# snarc.net
KiCad netlist of a schematic drawn in EAGLE
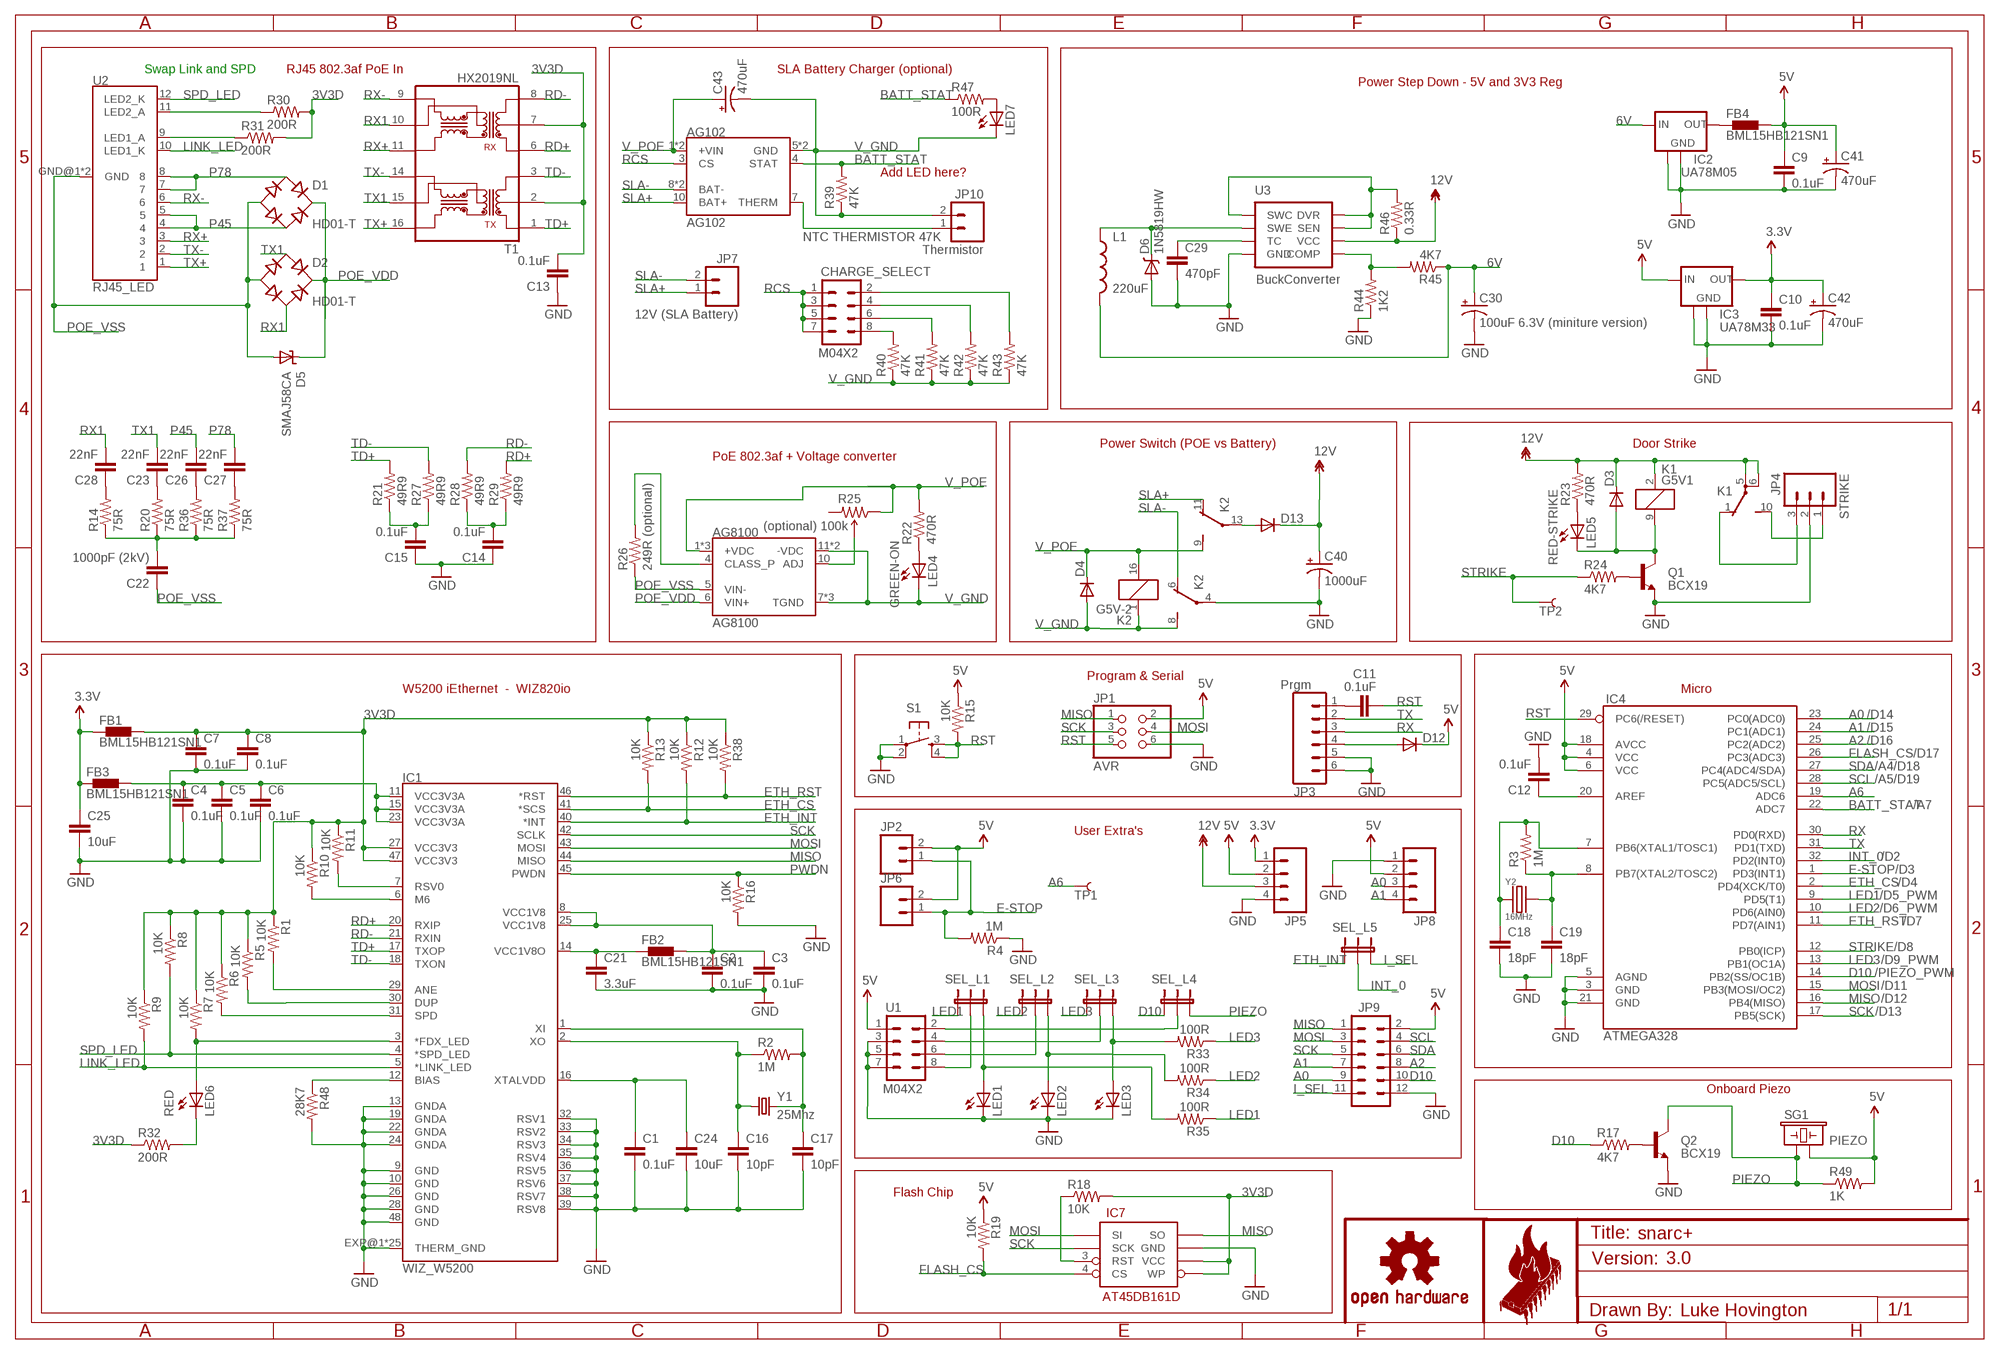
[diagram p0: schematic, sheet 1]

(export (version "E")
  (design (tool "Eeschema 10.0.6"))
  (components
    (comp (ref "AG102")
      (value "AG102")
      (footprint "eagle-import:AG102")
      (libsource (lib "eagle-import") (part "AG102"))
    )
    (comp (ref "AG8100")
      (value "AG8100")
      (footprint "eagle-import:AG8100")
      (libsource (lib "eagle-import") (part "AG8100"))
    )
    (comp (ref "C1")
      (value "0.1uF")
      (footprint "eagle-import:0402-CAP")
      (libsource (lib "eagle-import") (part "CAP0402-CAP"))
    )
    (comp (ref "C2")
      (value "0.1uF")
      (footprint "eagle-import:0402-CAP")
      (libsource (lib "eagle-import") (part "CAP0402-CAP"))
    )
    (comp (ref "C3")
      (value "0.1uF")
      (footprint "eagle-import:0402-CAP")
      (libsource (lib "eagle-import") (part "CAP0402-CAP"))
    )
    (comp (ref "C4")
      (value "0.1uF")
      (footprint "eagle-import:0402-CAP")
      (libsource (lib "eagle-import") (part "CAP0402-CAP"))
    )
    (comp (ref "C5")
      (value "0.1uF")
      (footprint "eagle-import:0402-CAP")
      (libsource (lib "eagle-import") (part "CAP0402-CAP"))
    )
    (comp (ref "C6")
      (value "0.1uF")
      (footprint "eagle-import:0402-CAP")
      (libsource (lib "eagle-import") (part "CAP0402-CAP"))
    )
    (comp (ref "C7")
      (value "0.1uF")
      (footprint "eagle-import:0402-CAP")
      (libsource (lib "eagle-import") (part "CAP0402-CAP"))
    )
    (comp (ref "C8")
      (value "0.1uF")
      (footprint "eagle-import:0402-CAP")
      (libsource (lib "eagle-import") (part "CAP0402-CAP"))
    )
    (comp (ref "C9")
      (value "0.1uF")
      (footprint "eagle-import:0402-CAP")
      (libsource (lib "eagle-import") (part "CAP0402-CAP"))
    )
    (comp (ref "C10")
      (value "0.1uF")
      (footprint "eagle-import:0402-CAP")
      (libsource (lib "eagle-import") (part "CAP0402-CAP"))
    )
    (comp (ref "C11")
      (value "0.1uF")
      (footprint "eagle-import:0402-CAP")
      (libsource (lib "eagle-import") (part "CAP0402-CAP"))
    )
    (comp (ref "C12")
      (value "0.1uF")
      (footprint "eagle-import:0402-CAP")
      (libsource (lib "eagle-import") (part "CAP0402-CAP"))
    )
    (comp (ref "C13")
      (value "0.1uF")
      (footprint "eagle-import:0402-CAP")
      (libsource (lib "eagle-import") (part "CAP0402-CAP"))
    )
    (comp (ref "C14")
      (value "0.1uF")
      (footprint "eagle-import:0402-CAP")
      (libsource (lib "eagle-import") (part "CAP0402-CAP"))
    )
    (comp (ref "C15")
      (value "0.1uF")
      (footprint "eagle-import:0402-CAP")
      (libsource (lib "eagle-import") (part "CAP0402-CAP"))
    )
    (comp (ref "C16")
      (value "10pF")
      (footprint "eagle-import:0402-CAP")
      (libsource (lib "eagle-import") (part "CAP0402-CAP"))
    )
    (comp (ref "C17")
      (value "10pF")
      (footprint "eagle-import:0402-CAP")
      (libsource (lib "eagle-import") (part "CAP0402-CAP"))
    )
    (comp (ref "C18")
      (value "18pF")
      (footprint "eagle-import:0402-CAP")
      (libsource (lib "eagle-import") (part "CAP0402-CAP"))
    )
    (comp (ref "C19")
      (value "18pF")
      (footprint "eagle-import:0402-CAP")
      (libsource (lib "eagle-import") (part "CAP0402-CAP"))
    )
    (comp (ref "C21")
      (value "3.3uF")
      (footprint "eagle-import:0402-CAP")
      (libsource (lib "eagle-import") (part "CAP0402-CAP"))
    )
    (comp (ref "C22")
      (value "1000pF (2kV)")
      (footprint "eagle-import:0402-CAP")
      (libsource (lib "eagle-import") (part "CAP0402-CAP"))
    )
    (comp (ref "C23")
      (value "22nF")
      (footprint "eagle-import:0402-CAP")
      (libsource (lib "eagle-import") (part "CAP0402-CAP"))
    )
    (comp (ref "C24")
      (value "10uF")
      (footprint "eagle-import:0603-CAP")
      (libsource (lib "eagle-import") (part "CAP0603-CAP"))
    )
    (comp (ref "C25")
      (value "10uF")
      (footprint "eagle-import:0603-CAP")
      (libsource (lib "eagle-import") (part "CAP0603-CAP"))
    )
    (comp (ref "C26")
      (value "22nF")
      (footprint "eagle-import:0402-CAP")
      (libsource (lib "eagle-import") (part "CAP0402-CAP"))
    )
    (comp (ref "C27")
      (value "22nF")
      (footprint "eagle-import:0402-CAP")
      (libsource (lib "eagle-import") (part "CAP0402-CAP"))
    )
    (comp (ref "C28")
      (value "22nF")
      (footprint "eagle-import:0402-CAP")
      (libsource (lib "eagle-import") (part "CAP0402-CAP"))
    )
    (comp (ref "C29")
      (value "470pF")
      (footprint "eagle-import:0402-CAP")
      (libsource (lib "eagle-import") (part "CAP0402-CAP"))
    )
    (comp (ref "C30")
      (value "100uF 6.3V (miniture version)")
      (footprint "eagle-import:PANASONIC_C")
      (libsource (lib "eagle-import") (part "CAP_POLC"))
    )
    (comp (ref "C40")
      (value "1000uF")
      (footprint "eagle-import:PANASONIC_H13")
      (libsource (lib "eagle-import") (part "CAP_POLH13"))
    )
    (comp (ref "C41")
      (value "470uF")
      (footprint "eagle-import:PANASONIC_E")
      (libsource (lib "eagle-import") (part "CAP_POLE"))
    )
    (comp (ref "C42")
      (value "470uF")
      (footprint "eagle-import:PANASONIC_E")
      (libsource (lib "eagle-import") (part "CAP_POLE"))
    )
    (comp (ref "C43")
      (value "470uF")
      (footprint "eagle-import:PANASONIC_E")
      (libsource (lib "eagle-import") (part "CAP_POLE"))
    )
    (comp (ref "CHARGE_SELECT")
      (value "M04X2")
      (footprint "eagle-import:2X4")
      (libsource (lib "eagle-import") (part "M04X2"))
    )
    (comp (ref "D1")
      (value "HD01-T")
      (footprint "eagle-import:MBS")
      (libsource (lib "eagle-import") (part "BS1"))
    )
    (comp (ref "D2")
      (value "HD01-T")
      (footprint "eagle-import:MBS")
      (libsource (lib "eagle-import") (part "BS1"))
    )
    (comp (ref "D3")
      (value "DIODESOD")
      (footprint "eagle-import:SOD-323")
      (libsource (lib "eagle-import") (part "DIODESOD"))
    )
    (comp (ref "D4")
      (value "DIODESOD")
      (footprint "eagle-import:SOD-323")
      (libsource (lib "eagle-import") (part "DIODESOD"))
    )
    (comp (ref "D5")
      (value "SMAJ58CA")
      (footprint "eagle-import:SMBJ")
      (libsource (lib "eagle-import") (part "SUPPRESSOR-SMBJ"))
    )
    (comp (ref "D6")
      (value "1N5819HW")
      (footprint "eagle-import:SOD-123")
      (libsource (lib "eagle-import") (part "DIODE-SCHOTTKYSOD-123"))
    )
    (comp (ref "D12")
      (value "DIODESOD")
      (footprint "eagle-import:SOD-323")
      (libsource (lib "eagle-import") (part "DIODESOD"))
    )
    (comp (ref "D13")
      (value "DIODESOD")
      (footprint "eagle-import:SOD-323")
      (libsource (lib "eagle-import") (part "DIODESOD"))
    )
    (comp (ref "FB1")
      (value "BML15HB121SN1")
      (footprint "eagle-import:0402")
      (libsource (lib "eagle-import") (part "BML15HB121SN1"))
    )
    (comp (ref "FB2")
      (value "BML15HB121SN1")
      (footprint "eagle-import:0402")
      (libsource (lib "eagle-import") (part "BML15HB121SN1"))
    )
    (comp (ref "FB3")
      (value "BML15HB121SN1")
      (footprint "eagle-import:0402")
      (libsource (lib "eagle-import") (part "BML15HB121SN1"))
    )
    (comp (ref "FB4")
      (value "BML15HB121SN1")
      (footprint "eagle-import:0402")
      (libsource (lib "eagle-import") (part "BML15HB121SN1"))
    )
    (comp (ref "IC1")
      (value "WIZ_W5200")
      (footprint "eagle-import:QFN48")
      (libsource (lib "eagle-import") (part "WIZ_W5200"))
    )
    (comp (ref "IC2")
      (value "UA78M05")
      (footprint "eagle-import:SOT223")
      (libsource (lib "eagle-import") (part "V_REG_SOTXXX"))
    )
    (comp (ref "IC3")
      (value "UA78M33")
      (footprint "eagle-import:SOT223")
      (libsource (lib "eagle-import") (part "V_REG_SOTXXX"))
    )
    (comp (ref "IC4")
      (value "ATMEGA328")
      (footprint "eagle-import:TQFP32-08")
      (libsource (lib "eagle-import") (part "ATMEGA168"))
    )
    (comp (ref "IC7")
      (value "AT45DB161D")
      (footprint "eagle-import:SO08-EIAJ")
      (libsource (lib "eagle-import") (part "AT45DB161D"))
    )
    (comp (ref "JP1")
      (value "AVR")
      (footprint "eagle-import:2X03")
      (libsource (lib "eagle-import") (part "PINHD-2X3"))
    )
    (comp (ref "JP2")
      (value "M023.5MM")
      (footprint "eagle-import:SCREWTERMINAL-3.5MM-2")
      (libsource (lib "eagle-import") (part "M023.5MM"))
    )
    (comp (ref "JP3")
      (value "Prgm")
      (footprint "eagle-import:1X06_SMD_STRAIGHT")
      (libsource (lib "eagle-import") (part "M06SMD-STRAIGHT"))
    )
    (comp (ref "JP4")
      (value "STRIKE")
      (footprint "eagle-import:SCREWTERMINAL-3.5MM-3")
      (libsource (lib "eagle-import") (part "M03SCREW"))
    )
    (comp (ref "JP5")
      (value "M04SMD")
      (footprint "eagle-import:1X04-SMD")
      (libsource (lib "eagle-import") (part "M04SMD"))
    )
    (comp (ref "JP6")
      (value "M021X02_NO_SILK")
      (footprint "eagle-import:1X02_NO_SILK")
      (libsource (lib "eagle-import") (part "M021X02_NO_SILK"))
    )
    (comp (ref "JP7")
      (value "12V (SLA Battery)")
      (footprint "eagle-import:SCREWTERMINAL-3.5MM-2")
      (libsource (lib "eagle-import") (part "M023.5MM"))
    )
    (comp (ref "JP8")
      (value "M04POLAR")
      (footprint "eagle-import:MOLEX-1X4")
      (libsource (lib "eagle-import") (part "M04POLAR"))
    )
    (comp (ref "JP9")
      (value "M05x2_SMD")
      (footprint "eagle-import:2X6-SHROUDED_SMD")
      (libsource (lib "eagle-import") (part "M06X2"))
    )
    (comp (ref "JP10")
      (value "Thermistor")
      (footprint "eagle-import:SCREWTERMINAL-3.5MM-2")
      (libsource (lib "eagle-import") (part "M023.5MM"))
    )
    (comp (ref "K1")
      (value "G5V1")
      (footprint "eagle-import:G5V1")
      (fields
        (field (name "MPN") "G5V-1-DC24")
        (field (name "MPN_1") "G5V-1-DC24")
        (field (name "OC_FARNELL") "9949593")
        (field (name "OC_NEWARK") "36M6377")
      )
      (libsource (lib "eagle-import") (part "G5V1"))
    )
    (comp (ref "K2")
      (value "G5V-2")
      (footprint "eagle-import:G5V-2")
      (fields (field (name "MPN") "G5V-2 5DC"))
      (libsource (lib "eagle-import") (part "G5V-2"))
    )
    (comp (ref "L1")
      (value "220uF")
      (footprint "eagle-import:SRN")
      (libsource (lib "eagle-import") (part "INDUCTOR"))
    )
    (comp (ref "LED1")
      (value "LED0603")
      (footprint "eagle-import:LED-0603")
      (libsource (lib "eagle-import") (part "LED0603"))
    )
    (comp (ref "LED2")
      (value "LED0603")
      (footprint "eagle-import:LED-0603")
      (libsource (lib "eagle-import") (part "LED0603"))
    )
    (comp (ref "LED3")
      (value "LED0603")
      (footprint "eagle-import:LED-0603")
      (libsource (lib "eagle-import") (part "LED0603"))
    )
    (comp (ref "LED4")
      (value "GREEN-ON")
      (footprint "eagle-import:LED-0603")
      (libsource (lib "eagle-import") (part "LED0603"))
    )
    (comp (ref "LED5")
      (value "RED-STRIKE")
      (footprint "eagle-import:LED-0603")
      (libsource (lib "eagle-import") (part "LED0603"))
    )
    (comp (ref "LED6")
      (value "RED")
      (footprint "eagle-import:LED-0603")
      (libsource (lib "eagle-import") (part "LED0603"))
    )
    (comp (ref "LED7")
      (value "LED0603")
      (footprint "eagle-import:LED-0603")
      (libsource (lib "eagle-import") (part "LED0603"))
    )
    (comp (ref "Q1")
      (value "BCX19")
      (footprint "eagle-import:SOT23-3")
      (libsource (lib "eagle-import") (part "TRANSISTOR_NPNSOT23-3"))
    )
    (comp (ref "Q2")
      (value "BCX19")
      (footprint "eagle-import:SOT23-3")
      (libsource (lib "eagle-import") (part "TRANSISTOR_NPNSOT23-3"))
    )
    (comp (ref "R1")
      (value "10K")
      (footprint "eagle-import:0402-RES")
      (libsource (lib "eagle-import") (part "RESISTOR0402-RES"))
    )
    (comp (ref "R2")
      (value "1M")
      (footprint "eagle-import:0402-RES")
      (libsource (lib "eagle-import") (part "RESISTOR0402-RES"))
    )
    (comp (ref "R3")
      (value "1M")
      (footprint "eagle-import:0402-RES")
      (libsource (lib "eagle-import") (part "RESISTOR0402-RES"))
    )
    (comp (ref "R4")
      (value "1M")
      (footprint "eagle-import:0603-RES")
      (libsource (lib "eagle-import") (part "RESISTOR0603-RES"))
    )
    (comp (ref "R5")
      (value "10K")
      (footprint "eagle-import:0402-RES")
      (libsource (lib "eagle-import") (part "RESISTOR0402-RES"))
    )
    (comp (ref "R6")
      (value "10K")
      (footprint "eagle-import:0402-RES")
      (libsource (lib "eagle-import") (part "RESISTOR0402-RES"))
    )
    (comp (ref "R7")
      (value "10K")
      (footprint "eagle-import:0402-RES")
      (libsource (lib "eagle-import") (part "RESISTOR0402-RES"))
    )
    (comp (ref "R8")
      (value "10K")
      (footprint "eagle-import:0402-RES")
      (libsource (lib "eagle-import") (part "RESISTOR0402-RES"))
    )
    (comp (ref "R9")
      (value "10K")
      (footprint "eagle-import:0402-RES")
      (libsource (lib "eagle-import") (part "RESISTOR0402-RES"))
    )
    (comp (ref "R10")
      (value "10K")
      (footprint "eagle-import:0402-RES")
      (libsource (lib "eagle-import") (part "RESISTOR0402-RES"))
    )
    (comp (ref "R11")
      (value "10K")
      (footprint "eagle-import:0402-RES")
      (libsource (lib "eagle-import") (part "RESISTOR0402-RES"))
    )
    (comp (ref "R12")
      (value "10K")
      (footprint "eagle-import:0402-RES")
      (libsource (lib "eagle-import") (part "RESISTOR0402-RES"))
    )
    (comp (ref "R13")
      (value "10K")
      (footprint "eagle-import:0402-RES")
      (libsource (lib "eagle-import") (part "RESISTOR0402-RES"))
    )
    (comp (ref "R14")
      (value "75R")
      (footprint "eagle-import:0402-RES")
      (libsource (lib "eagle-import") (part "RESISTOR0402-RES"))
    )
    (comp (ref "R15")
      (value "10K")
      (footprint "eagle-import:0402-RES")
      (libsource (lib "eagle-import") (part "RESISTOR0402-RES"))
    )
    (comp (ref "R16")
      (value "10K")
      (footprint "eagle-import:0402-RES")
      (libsource (lib "eagle-import") (part "RESISTOR0402-RES"))
    )
    (comp (ref "R17")
      (value "4K7")
      (footprint "eagle-import:0402-RES")
      (libsource (lib "eagle-import") (part "RESISTOR0402-RES"))
    )
    (comp (ref "R18")
      (value "10K")
      (footprint "eagle-import:0402-RES")
      (libsource (lib "eagle-import") (part "RESISTOR0402-RES"))
    )
    (comp (ref "R19")
      (value "10K")
      (footprint "eagle-import:0402-RES")
      (libsource (lib "eagle-import") (part "RESISTOR0402-RES"))
    )
    (comp (ref "R20")
      (value "75R")
      (footprint "eagle-import:0402-RES")
      (libsource (lib "eagle-import") (part "RESISTOR0402-RES"))
    )
    (comp (ref "R21")
      (value "49R9")
      (footprint "eagle-import:0402-RES")
      (libsource (lib "eagle-import") (part "RESISTOR0402-RES"))
    )
    (comp (ref "R22")
      (value "470R")
      (footprint "eagle-import:0402-RES")
      (libsource (lib "eagle-import") (part "RESISTOR0402-RES"))
    )
    (comp (ref "R23")
      (value "470R")
      (footprint "eagle-import:0402-RES")
      (libsource (lib "eagle-import") (part "RESISTOR0402-RES"))
    )
    (comp (ref "R24")
      (value "4K7")
      (footprint "eagle-import:0402-RES")
      (libsource (lib "eagle-import") (part "RESISTOR0402-RES"))
    )
    (comp (ref "R25")
      (value "(optional) 100k")
      (footprint "eagle-import:TRIMPOT-3MM")
      (libsource (lib "eagle-import") (part "TRIMPOTSMD"))
    )
    (comp (ref "R26")
      (value "249R (optional)")
      (footprint "eagle-import:1206")
      (libsource (lib "eagle-import") (part "RESISTOR1206"))
    )
    (comp (ref "R27")
      (value "49R9")
      (footprint "eagle-import:0402-RES")
      (libsource (lib "eagle-import") (part "RESISTOR0402-RES"))
    )
    (comp (ref "R28")
      (value "49R9")
      (footprint "eagle-import:0402-RES")
      (libsource (lib "eagle-import") (part "RESISTOR0402-RES"))
    )
    (comp (ref "R29")
      (value "49R9")
      (footprint "eagle-import:0402-RES")
      (libsource (lib "eagle-import") (part "RESISTOR0402-RES"))
    )
    (comp (ref "R30")
      (value "200R")
      (footprint "eagle-import:0402-RES")
      (libsource (lib "eagle-import") (part "RESISTOR0402-RES"))
    )
    (comp (ref "R31")
      (value "200R")
      (footprint "eagle-import:0402-RES")
      (libsource (lib "eagle-import") (part "RESISTOR0402-RES"))
    )
    (comp (ref "R32")
      (value "200R")
      (footprint "eagle-import:0402-RES")
      (libsource (lib "eagle-import") (part "RESISTOR0402-RES"))
    )
    (comp (ref "R33")
      (value "100R")
      (footprint "eagle-import:0402-RES")
      (libsource (lib "eagle-import") (part "RESISTOR0402-RES"))
    )
    (comp (ref "R34")
      (value "100R")
      (footprint "eagle-import:0402-RES")
      (libsource (lib "eagle-import") (part "RESISTOR0402-RES"))
    )
    (comp (ref "R35")
      (value "100R")
      (footprint "eagle-import:0402-RES")
      (libsource (lib "eagle-import") (part "RESISTOR0402-RES"))
    )
    (comp (ref "R36")
      (value "75R")
      (footprint "eagle-import:0402-RES")
      (libsource (lib "eagle-import") (part "RESISTOR0402-RES"))
    )
    (comp (ref "R37")
      (value "75R")
      (footprint "eagle-import:0402-RES")
      (libsource (lib "eagle-import") (part "RESISTOR0402-RES"))
    )
    (comp (ref "R38")
      (value "10K")
      (footprint "eagle-import:0402-RES")
      (libsource (lib "eagle-import") (part "RESISTOR0402-RES"))
    )
    (comp (ref "R39")
      (value "47K")
      (footprint "eagle-import:0402-RES")
      (libsource (lib "eagle-import") (part "RESISTOR0402-RES"))
    )
    (comp (ref "R40")
      (value "47K")
      (footprint "eagle-import:0402-RES")
      (libsource (lib "eagle-import") (part "RESISTOR0402-RES"))
    )
    (comp (ref "R41")
      (value "47K")
      (footprint "eagle-import:0402-RES")
      (libsource (lib "eagle-import") (part "RESISTOR0402-RES"))
    )
    (comp (ref "R42")
      (value "47K")
      (footprint "eagle-import:0402-RES")
      (libsource (lib "eagle-import") (part "RESISTOR0402-RES"))
    )
    (comp (ref "R43")
      (value "47K")
      (footprint "eagle-import:0402-RES")
      (libsource (lib "eagle-import") (part "RESISTOR0402-RES"))
    )
    (comp (ref "R44")
      (value "1K2")
      (footprint "eagle-import:0402-RES")
      (libsource (lib "eagle-import") (part "RESISTOR0402-RES"))
    )
    (comp (ref "R45")
      (value "4K7")
      (footprint "eagle-import:0402-RES")
      (libsource (lib "eagle-import") (part "RESISTOR0402-RES"))
    )
    (comp (ref "R46")
      (value "0.33R")
      (footprint "eagle-import:0402-RES")
      (libsource (lib "eagle-import") (part "RESISTOR0402-RES"))
    )
    (comp (ref "R47")
      (value "100R")
      (footprint "eagle-import:0402-RES")
      (libsource (lib "eagle-import") (part "RESISTOR0402-RES"))
    )
    (comp (ref "R48")
      (value "28K7")
      (footprint "eagle-import:0402-RES")
      (libsource (lib "eagle-import") (part "RESISTOR0402-RES"))
    )
    (comp (ref "R49")
      (value "1K")
      (footprint "eagle-import:0402-RES")
      (libsource (lib "eagle-import") (part "RESISTOR0402-RES"))
    )
    (comp (ref "S1")
      (value "TAC_SWITCHSMD")
      (footprint "eagle-import:TACTILE_SWITCH_SMD")
      (libsource (lib "eagle-import") (part "TAC_SWITCHSMD"))
    )
    (comp (ref "SEL_L1")
      (value "JUMPER-32-3")
      (footprint "eagle-import:SJ_3_PASTE2&3")
      (libsource (lib "eagle-import") (part "JUMPER-32-3"))
    )
    (comp (ref "SEL_L2")
      (value "JUMPER-32-3")
      (footprint "eagle-import:SJ_3_PASTE2&3")
      (libsource (lib "eagle-import") (part "JUMPER-32-3"))
    )
    (comp (ref "SEL_L3")
      (value "JUMPER-32-3")
      (footprint "eagle-import:SJ_3_PASTE2&3")
      (libsource (lib "eagle-import") (part "JUMPER-32-3"))
    )
    (comp (ref "SEL_L4")
      (value "JUMPER-32-3")
      (footprint "eagle-import:SJ_3_PASTE2&3")
      (libsource (lib "eagle-import") (part "JUMPER-32-3"))
    )
    (comp (ref "SEL_L5")
      (value "JUMPER-32-3")
      (footprint "eagle-import:SJ_3_PASTE2&3")
      (libsource (lib "eagle-import") (part "JUMPER-32-3"))
    )
    (comp (ref "SG1")
      (value "PIEZO")
      (footprint "eagle-import:PB158-BUZZER")
      (libsource (lib "eagle-import") (part "BUZZER"))
    )
    (comp (ref "T1")
      (value "HX2019NL")
      (footprint "eagle-import:HXXXX")
      (libsource (lib "eagle-import") (part "HX1188"))
    )
    (comp (ref "TP1")
      (value "TEST-POINT3X5")
      (footprint "eagle-import:PAD.03X.05")
      (libsource (lib "eagle-import") (part "TEST-POINT3X5"))
    )
    (comp (ref "TP2")
      (value "TEST-POINT3X5")
      (footprint "eagle-import:PAD.03X.05")
      (libsource (lib "eagle-import") (part "TEST-POINT3X5"))
    )
    (comp (ref "U$15")
      (value "OSHW-LOGOL")
      (footprint "eagle-import:OSHW-LOGO-L")
      (libsource (lib "eagle-import") (part "OSHW-LOGOL"))
    )
    (comp (ref "U$16")
      (value "HSBNE_LOGOMED")
      (footprint "eagle-import:HSBNE_MED")
      (libsource (lib "eagle-import") (part "HSBNE_LOGOMED"))
    )
    (comp (ref "U1")
      (value "M04X2")
      (footprint "eagle-import:2X4")
      (libsource (lib "eagle-import") (part "M04X2"))
    )
    (comp (ref "U2")
      (value "RJ45_LED")
      (footprint "eagle-import:RJHSE-5484")
      (libsource (lib "eagle-import") (part "RJ45_LED"))
    )
    (comp (ref "U3")
      (value "BuckConverter")
      (footprint "eagle-import:SO08")
      (libsource (lib "eagle-import") (part "MC34063SMD"))
    )
    (comp (ref "Y1")
      (value "25Mhz")
      (footprint "eagle-import:CRYSTAL-SMD-2.5X2-ABM10")
      (libsource (lib "eagle-import") (part "CRYSTALABM10"))
    )
    (comp (ref "Y2")
      (value "16MHz")
      (footprint "eagle-import:XTAL-CSX750")
      (libsource (lib "eagle-import") (part "ABM8"))
    )
  )
  (nets
    (net (code "1") (name "/3V3D") (class "Default")
      (node (ref "C13") (pin "2") (pinfunction "2_2") (pintype "passive"))
      (node (ref "C7") (pin "1") (pinfunction "1_1") (pintype "passive"))
      (node (ref "C8") (pin "1") (pinfunction "1_1") (pintype "passive"))
      (node (ref "FB1") (pin "2") (pinfunction "2_2") (pintype "passive"))
      (node (ref "IC1") (pin "27") (pinfunction "VCC3V3_27") (pintype "bidirectional"))
      (node (ref "IC1") (pin "47") (pinfunction "VCC3V3_47") (pintype "bidirectional"))
      (node (ref "IC7") (pin "5") (pinfunction "WP_5") (pintype "bidirectional"))
      (node (ref "IC7") (pin "6") (pinfunction "VCC_6") (pintype "bidirectional"))
      (node (ref "R1") (pin "1") (pinfunction "1_1") (pintype "passive"))
      (node (ref "R10") (pin "1") (pinfunction "1_1") (pintype "passive"))
      (node (ref "R11") (pin "1") (pinfunction "1_1") (pintype "passive"))
      (node (ref "R12") (pin "1") (pinfunction "1_1") (pintype "passive"))
      (node (ref "R13") (pin "1") (pinfunction "1_1") (pintype "passive"))
      (node (ref "R18") (pin "2") (pinfunction "2_2") (pintype "passive"))
      (node (ref "R30") (pin "2") (pinfunction "2_2") (pintype "passive"))
      (node (ref "R31") (pin "2") (pinfunction "2_2") (pintype "passive"))
      (node (ref "R32") (pin "1") (pinfunction "1_1") (pintype "passive"))
      (node (ref "R38") (pin "1") (pinfunction "1_1") (pintype "passive"))
      (node (ref "R5") (pin "1") (pinfunction "1_1") (pintype "passive"))
      (node (ref "R6") (pin "1") (pinfunction "1_1") (pintype "passive"))
      (node (ref "R7") (pin "1") (pinfunction "1_1") (pintype "passive"))
      (node (ref "R8") (pin "1") (pinfunction "1_1") (pintype "passive"))
      (node (ref "R9") (pin "1") (pinfunction "1_1") (pintype "passive"))
      (node (ref "T1") (pin "2") (pinfunction "2_2") (pintype "passive"))
      (node (ref "T1") (pin "7") (pinfunction "7_7") (pintype "passive"))
    )
    (net (code "2") (name "/6V") (class "Default")
      (node (ref "C30") (pin "+") (pinfunction "+_+") (pintype "passive"))
      (node (ref "IC2") (pin "1") (pinfunction "IN_1") (pintype "input"))
      (node (ref "L1") (pin "P$2") (pinfunction "2_P$2") (pintype "passive"))
      (node (ref "R45") (pin "1") (pinfunction "1_1") (pintype "passive"))
    )
    (net (code "3") (name "/A0") (class "Default")
      (node (ref "IC4") (pin "23") (pinfunction "PC0(ADC0)_23") (pintype "bidirectional"))
      (node (ref "JP8") (pin "3") (pinfunction "3_3") (pintype "passive"))
      (node (ref "JP9") (pin "9") (pinfunction "9_9") (pintype "passive"))
    )
    (net (code "4") (name "/A1") (class "Default")
      (node (ref "IC4") (pin "24") (pinfunction "PC1(ADC1)_24") (pintype "bidirectional"))
      (node (ref "JP8") (pin "4") (pinfunction "4_4") (pintype "passive"))
      (node (ref "JP9") (pin "7") (pinfunction "7_7") (pintype "passive"))
    )
    (net (code "5") (name "/A2") (class "Default")
      (node (ref "IC4") (pin "25") (pinfunction "PC2(ADC2)_25") (pintype "bidirectional"))
      (node (ref "JP9") (pin "8") (pinfunction "8_8") (pintype "passive"))
    )
    (net (code "6") (name "/A6") (class "Default")
      (node (ref "IC4") (pin "19") (pinfunction "ADC6_19") (pintype "bidirectional"))
      (node (ref "TP1") (pin "P$1") (pinfunction "1_P$1") (pintype "bidirectional"))
    )
    (net (code "7") (name "/BATT_STAT") (class "Default")
      (node (ref "AG102") (pin "4") (pinfunction "STAT_4") (pintype "bidirectional"))
      (node (ref "IC4") (pin "22") (pinfunction "ADC7_22") (pintype "bidirectional"))
      (node (ref "R39") (pin "2") (pinfunction "2_2") (pintype "passive"))
      (node (ref "R47") (pin "1") (pinfunction "1_1") (pintype "passive"))
    )
    (net (code "8") (name "/D10") (class "Default")
      (node (ref "IC4") (pin "14") (pinfunction "PB2(SS/OC1B)_14") (pintype "bidirectional"))
      (node (ref "JP9") (pin "10") (pinfunction "10_10") (pintype "passive"))
      (node (ref "R17") (pin "1") (pinfunction "1_1") (pintype "passive"))
      (node (ref "SEL_L4") (pin "1") (pinfunction "1_1") (pintype "passive"))
    )
    (net (code "9") (name "/E-STOP") (class "Default")
      (node (ref "IC4") (pin "1") (pinfunction "PD3(INT1)_1") (pintype "bidirectional"))
      (node (ref "JP2") (pin "1") (pinfunction "1_1") (pintype "passive"))
      (node (ref "JP6") (pin "1") (pinfunction "1_1") (pintype "passive"))
      (node (ref "R4") (pin "2") (pinfunction "2_2") (pintype "passive"))
    )
    (net (code "10") (name "/ETH_CS") (class "Default")
      (node (ref "IC1") (pin "41") (pinfunction "*SCS_41") (pintype "bidirectional"))
      (node (ref "IC4") (pin "2") (pinfunction "PD4(XCK/T0)_2") (pintype "bidirectional"))
      (node (ref "R13") (pin "2") (pinfunction "2_2") (pintype "passive"))
    )
    (net (code "11") (name "/ETH_INT") (class "Default")
      (node (ref "IC1") (pin "40") (pinfunction "*INT_40") (pintype "bidirectional"))
      (node (ref "R12") (pin "2") (pinfunction "2_2") (pintype "passive"))
      (node (ref "SEL_L5") (pin "1") (pinfunction "1_1") (pintype "passive"))
    )
    (net (code "12") (name "/ETH_RST") (class "Default")
      (node (ref "IC1") (pin "46") (pinfunction "*RST_46") (pintype "bidirectional"))
      (node (ref "IC4") (pin "11") (pinfunction "PD7(AIN1)_11") (pintype "bidirectional"))
      (node (ref "R38") (pin "2") (pinfunction "2_2") (pintype "passive"))
    )
    (net (code "13") (name "/FLASH_CS") (class "Default")
      (node (ref "IC4") (pin "26") (pinfunction "PC3(ADC3)_26") (pintype "bidirectional"))
      (node (ref "IC7") (pin "4") (pinfunction "CS_4") (pintype "bidirectional"))
      (node (ref "R19") (pin "2") (pinfunction "2_2") (pintype "passive"))
    )
    (net (code "14") (name "/INT_0") (class "Default")
      (node (ref "IC4") (pin "32") (pinfunction "PD2(INT0)_32") (pintype "bidirectional"))
      (node (ref "SEL_L5") (pin "2") (pinfunction "2_2") (pintype "passive"))
    )
    (net (code "15") (name "/I_SEL") (class "Default")
      (node (ref "JP9") (pin "11") (pinfunction "11_11") (pintype "passive"))
      (node (ref "SEL_L5") (pin "3") (pinfunction "3_3") (pintype "passive"))
    )
    (net (code "16") (name "/LED1") (class "Default")
      (node (ref "IC4") (pin "9") (pinfunction "PD5(T1)_9") (pintype "bidirectional"))
      (node (ref "R35") (pin "1") (pinfunction "1_1") (pintype "passive"))
      (node (ref "SEL_L1") (pin "1") (pinfunction "1_1") (pintype "passive"))
    )
    (net (code "17") (name "/LED2") (class "Default")
      (node (ref "IC4") (pin "10") (pinfunction "PD6(AIN0)_10") (pintype "bidirectional"))
      (node (ref "R34") (pin "1") (pinfunction "1_1") (pintype "passive"))
      (node (ref "SEL_L2") (pin "1") (pinfunction "1_1") (pintype "passive"))
    )
    (net (code "18") (name "/LED3") (class "Default")
      (node (ref "IC4") (pin "13") (pinfunction "PB1(OC1A)_13") (pintype "bidirectional"))
      (node (ref "R33") (pin "1") (pinfunction "1_1") (pintype "passive"))
      (node (ref "SEL_L3") (pin "1") (pinfunction "1_1") (pintype "passive"))
    )
    (net (code "19") (name "/LINK_LED") (class "Default")
      (node (ref "IC1") (pin "5") (pinfunction "*LINK_LED_5") (pintype "bidirectional"))
      (node (ref "R9") (pin "2") (pinfunction "2_2") (pintype "passive"))
      (node (ref "U2") (pin "10") (pinfunction "LED1_K_10") (pintype "bidirectional"))
    )
    (net (code "20") (name "/MISO") (class "Default")
      (node (ref "IC1") (pin "44") (pinfunction "MISO_44") (pintype "bidirectional"))
      (node (ref "IC4") (pin "16") (pinfunction "PB4(MISO)_16") (pintype "bidirectional"))
      (node (ref "IC7") (pin "8") (pinfunction "SO_8") (pintype "bidirectional"))
      (node (ref "JP1") (pin "1") (pinfunction "1_1") (pintype "passive"))
      (node (ref "JP9") (pin "1") (pinfunction "1_1") (pintype "passive"))
    )
    (net (code "21") (name "/MOSI") (class "Default")
      (node (ref "IC1") (pin "43") (pinfunction "MOSI_43") (pintype "bidirectional"))
      (node (ref "IC4") (pin "15") (pinfunction "PB3(MOSI/OC2)_15") (pintype "bidirectional"))
      (node (ref "IC7") (pin "1") (pinfunction "SI_1") (pintype "bidirectional"))
      (node (ref "JP1") (pin "4") (pinfunction "4_4") (pintype "passive"))
      (node (ref "JP9") (pin "3") (pinfunction "3_3") (pintype "passive"))
    )
    (net (code "22") (name "/P45") (class "Default")
      (node (ref "C26") (pin "2") (pinfunction "2_2") (pintype "passive"))
      (node (ref "D1") (pin "AC2") (pinfunction "AC2_AC2") (pintype "passive"))
      (node (ref "U2") (pin "4") (pinfunction "4_4") (pintype "bidirectional"))
      (node (ref "U2") (pin "5") (pinfunction "5_5") (pintype "bidirectional"))
    )
    (net (code "23") (name "/P78") (class "Default")
      (node (ref "C27") (pin "2") (pinfunction "2_2") (pintype "passive"))
      (node (ref "D1") (pin "AC1") (pinfunction "AC1_AC1") (pintype "passive"))
      (node (ref "U2") (pin "7") (pinfunction "7_7") (pintype "bidirectional"))
      (node (ref "U2") (pin "8") (pinfunction "8_8") (pintype "bidirectional"))
    )
    (net (code "24") (name "/PIEZO") (class "Default")
      (node (ref "Q2") (pin "3") (pinfunction "C_3") (pintype "passive"))
      (node (ref "R49") (pin "1") (pinfunction "1_1") (pintype "passive"))
      (node (ref "SEL_L4") (pin "3") (pinfunction "3_3") (pintype "passive"))
      (node (ref "SG1") (pin "P$1") (pinfunction "1_P$1") (pintype "passive"))
    )
    (net (code "25") (name "/POE_VDD") (class "Default")
      (node (ref "AG8100") (pin "6") (pinfunction "VIN+_6") (pintype "bidirectional"))
      (node (ref "D1") (pin "+") (pinfunction "+_+") (pintype "passive"))
      (node (ref "D2") (pin "+") (pinfunction "+_+") (pintype "passive"))
      (node (ref "D5") (pin "C") (pinfunction "C_C") (pintype "passive"))
    )
    (net (code "26") (name "/POE_VSS") (class "Default")
      (node (ref "AG8100") (pin "5") (pinfunction "VIN-_5") (pintype "bidirectional"))
      (node (ref "C22") (pin "1") (pinfunction "1_1") (pintype "passive"))
      (node (ref "D1") (pin "-") (pinfunction "-_-") (pintype "passive"))
      (node (ref "D2") (pin "-") (pinfunction "-_-") (pintype "passive"))
      (node (ref "D5") (pin "A") (pinfunction "A_A") (pintype "passive"))
      (node (ref "R26") (pin "1") (pinfunction "1_1") (pintype "passive"))
      (node (ref "U2") (pin "GND@1") (pinfunction "GND_GND@1") (pintype "bidirectional"))
      (node (ref "U2") (pin "GND@2") (pinfunction "GND_GND@2") (pintype "bidirectional"))
    )
    (net (code "27") (name "/PWDN") (class "Default")
      (node (ref "IC1") (pin "45") (pinfunction "PWDN_45") (pintype "bidirectional"))
      (node (ref "R16") (pin "1") (pinfunction "1_1") (pintype "passive"))
    )
    (net (code "28") (name "/RCS") (class "Default")
      (node (ref "AG102") (pin "3") (pinfunction "CS_3") (pintype "bidirectional"))
      (node (ref "CHARGE_SELECT") (pin "1") (pinfunction "1_1") (pintype "passive"))
      (node (ref "CHARGE_SELECT") (pin "3") (pinfunction "3_3") (pintype "passive"))
      (node (ref "CHARGE_SELECT") (pin "5") (pinfunction "5_5") (pintype "passive"))
      (node (ref "CHARGE_SELECT") (pin "7") (pinfunction "7_7") (pintype "passive"))
    )
    (net (code "29") (name "/RD+") (class "Default")
      (node (ref "IC1") (pin "20") (pinfunction "RXIP_20") (pintype "bidirectional"))
      (node (ref "R29") (pin "2") (pinfunction "2_2") (pintype "passive"))
      (node (ref "T1") (pin "6") (pinfunction "6_6") (pintype "passive"))
    )
    (net (code "30") (name "/RD-") (class "Default")
      (node (ref "IC1") (pin "21") (pinfunction "RXIN_21") (pintype "bidirectional"))
      (node (ref "R28") (pin "2") (pinfunction "2_2") (pintype "passive"))
      (node (ref "T1") (pin "8") (pinfunction "8_8") (pintype "passive"))
    )
    (net (code "31") (name "/RST") (class "Default")
      (node (ref "C11") (pin "1") (pinfunction "1_1") (pintype "passive"))
      (node (ref "IC4") (pin "29") (pinfunction "PC6(/RESET)_29") (pintype "bidirectional"))
      (node (ref "JP1") (pin "5") (pinfunction "5_5") (pintype "passive"))
      (node (ref "R15") (pin "2") (pinfunction "2_2") (pintype "passive"))
      (node (ref "S1") (pin "3") (pinfunction "3_3") (pintype "passive"))
      (node (ref "S1") (pin "4") (pinfunction "4_4") (pintype "passive"))
    )
    (net (code "32") (name "/RX") (class "Default")
      (node (ref "IC4") (pin "30") (pinfunction "PD0(RXD)_30") (pintype "bidirectional"))
      (node (ref "JP3") (pin "3") (pinfunction "3_3") (pintype "passive"))
    )
    (net (code "33") (name "/RX+") (class "Default")
      (node (ref "T1") (pin "11") (pinfunction "11_11") (pintype "passive"))
      (node (ref "U2") (pin "3") (pinfunction "3_3") (pintype "bidirectional"))
    )
    (net (code "34") (name "/RX-") (class "Default")
      (node (ref "T1") (pin "9") (pinfunction "9_9") (pintype "passive"))
      (node (ref "U2") (pin "6") (pinfunction "6_6") (pintype "bidirectional"))
    )
    (net (code "35") (name "/RX1") (class "Default")
      (node (ref "C28") (pin "2") (pinfunction "2_2") (pintype "passive"))
      (node (ref "D2") (pin "AC2") (pinfunction "AC2_AC2") (pintype "passive"))
      (node (ref "T1") (pin "10") (pinfunction "10_10") (pintype "passive"))
    )
    (net (code "36") (name "/SCK") (class "Default")
      (node (ref "IC1") (pin "42") (pinfunction "SCLK_42") (pintype "bidirectional"))
      (node (ref "IC4") (pin "17") (pinfunction "PB5(SCK)_17") (pintype "bidirectional"))
      (node (ref "IC7") (pin "2") (pinfunction "SCK_2") (pintype "bidirectional"))
      (node (ref "JP1") (pin "3") (pinfunction "3_3") (pintype "passive"))
      (node (ref "JP9") (pin "5") (pinfunction "5_5") (pintype "passive"))
    )
    (net (code "37") (name "/SCL") (class "Default")
      (node (ref "IC4") (pin "28") (pinfunction "PC5(ADC5/SCL)_28") (pintype "bidirectional"))
      (node (ref "JP9") (pin "4") (pinfunction "4_4") (pintype "passive"))
    )
    (net (code "38") (name "/SDA") (class "Default")
      (node (ref "IC4") (pin "27") (pinfunction "PC4(ADC4/SDA)_27") (pintype "bidirectional"))
      (node (ref "JP9") (pin "6") (pinfunction "6_6") (pintype "passive"))
    )
    (net (code "39") (name "/SLA+") (class "Default")
      (node (ref "AG102") (pin "10") (pinfunction "BAT+_10") (pintype "bidirectional"))
      (node (ref "JP7") (pin "1") (pinfunction "1_1") (pintype "passive"))
      (node (ref "K2") (pin "11") (pinfunction "O_11") (pintype "passive"))
    )
    (net (code "40") (name "/SLA-") (class "Default")
      (node (ref "AG102") (pin "8") (pinfunction "BAT-_8") (pintype "bidirectional"))
      (node (ref "AG102") (pin "9") (pinfunction "BAT-_9") (pintype "bidirectional"))
      (node (ref "JP7") (pin "2") (pinfunction "2_2") (pintype "passive"))
      (node (ref "K2") (pin "6") (pinfunction "O_6") (pintype "passive"))
    )
    (net (code "41") (name "/SPD_LED") (class "Default")
      (node (ref "IC1") (pin "4") (pinfunction "*SPD_LED_4") (pintype "bidirectional"))
      (node (ref "R8") (pin "2") (pinfunction "2_2") (pintype "passive"))
      (node (ref "U2") (pin "12") (pinfunction "LED2_K_12") (pintype "bidirectional"))
    )
    (net (code "42") (name "/STRIKE") (class "Default")
      (node (ref "IC4") (pin "12") (pinfunction "PB0(ICP)_12") (pintype "bidirectional"))
      (node (ref "R24") (pin "1") (pinfunction "1_1") (pintype "passive"))
      (node (ref "TP2") (pin "P$1") (pinfunction "1_P$1") (pintype "bidirectional"))
    )
    (net (code "43") (name "/TD+") (class "Default")
      (node (ref "IC1") (pin "17") (pinfunction "TXOP_17") (pintype "bidirectional"))
      (node (ref "R21") (pin "2") (pinfunction "2_2") (pintype "passive"))
      (node (ref "T1") (pin "1") (pinfunction "1_1") (pintype "passive"))
    )
    (net (code "44") (name "/TD-") (class "Default")
      (node (ref "IC1") (pin "18") (pinfunction "TXON_18") (pintype "bidirectional"))
      (node (ref "R27") (pin "2") (pinfunction "2_2") (pintype "passive"))
      (node (ref "T1") (pin "3") (pinfunction "3_3") (pintype "passive"))
    )
    (net (code "45") (name "/TX") (class "Default")
      (node (ref "IC4") (pin "31") (pinfunction "PD1(TXD)_31") (pintype "bidirectional"))
      (node (ref "JP3") (pin "2") (pinfunction "2_2") (pintype "passive"))
    )
    (net (code "46") (name "/TX+") (class "Default")
      (node (ref "T1") (pin "16") (pinfunction "16_16") (pintype "passive"))
      (node (ref "U2") (pin "1") (pinfunction "1_1") (pintype "bidirectional"))
    )
    (net (code "47") (name "/TX-") (class "Default")
      (node (ref "T1") (pin "14") (pinfunction "14_14") (pintype "passive"))
      (node (ref "U2") (pin "2") (pinfunction "2_2") (pintype "bidirectional"))
    )
    (net (code "48") (name "/TX1") (class "Default")
      (node (ref "C23") (pin "2") (pinfunction "2_2") (pintype "passive"))
      (node (ref "D2") (pin "AC1") (pinfunction "AC1_AC1") (pintype "passive"))
      (node (ref "T1") (pin "15") (pinfunction "15_15") (pintype "passive"))
    )
    (net (code "49") (name "/V_GND") (class "Default")
      (node (ref "AG102") (pin "5") (pinfunction "GND_5") (pintype "bidirectional"))
      (node (ref "AG102") (pin "6") (pinfunction "GND_6") (pintype "bidirectional"))
      (node (ref "AG8100") (pin "11") (pinfunction "-VDC_11") (pintype "bidirectional"))
      (node (ref "AG8100") (pin "12") (pinfunction "-VDC_12") (pintype "bidirectional"))
      (node (ref "AG8100") (pin "7") (pinfunction "TGND_7") (pintype "bidirectional"))
      (node (ref "AG8100") (pin "8") (pinfunction "TGND_8") (pintype "bidirectional"))
      (node (ref "AG8100") (pin "9") (pinfunction "TGND_9") (pintype "bidirectional"))
      (node (ref "C43") (pin "-") (pinfunction "-_-") (pintype "passive"))
      (node (ref "D4") (pin "2") (pinfunction "A_2") (pintype "passive"))
      (node (ref "JP10") (pin "2") (pinfunction "2_2") (pintype "passive"))
      (node (ref "K2") (pin "1") (pinfunction "1_1") (pintype "passive"))
      (node (ref "K2") (pin "8") (pinfunction "S_8") (pintype "passive"))
      (node (ref "LED4") (pin "C") (pinfunction "C_C") (pintype "passive"))
      (node (ref "LED7") (pin "C") (pinfunction "C_C") (pintype "passive"))
      (node (ref "R39") (pin "1") (pinfunction "1_1") (pintype "passive"))
      (node (ref "R40") (pin "1") (pinfunction "1_1") (pintype "passive"))
      (node (ref "R41") (pin "1") (pinfunction "1_1") (pintype "passive"))
      (node (ref "R42") (pin "1") (pinfunction "1_1") (pintype "passive"))
      (node (ref "R43") (pin "1") (pinfunction "1_1") (pintype "passive"))
    )
    (net (code "50") (name "/V_POE") (class "Default")
      (node (ref "AG102") (pin "1") (pinfunction "+VIN_1") (pintype "bidirectional"))
      (node (ref "AG102") (pin "2") (pinfunction "+VIN_2") (pintype "bidirectional"))
      (node (ref "AG8100") (pin "1") (pinfunction "+VDC_1") (pintype "bidirectional"))
      (node (ref "AG8100") (pin "2") (pinfunction "+VDC_2") (pintype "bidirectional"))
      (node (ref "AG8100") (pin "3") (pinfunction "+VDC_3") (pintype "bidirectional"))
      (node (ref "C43") (pin "+") (pinfunction "+_+") (pintype "passive"))
      (node (ref "D4") (pin "1") (pinfunction "C_1") (pintype "passive"))
      (node (ref "K2") (pin "16") (pinfunction "2_16") (pintype "passive"))
      (node (ref "K2") (pin "9") (pinfunction "S_9") (pintype "passive"))
      (node (ref "R22") (pin "2") (pinfunction "2_2") (pintype "passive"))
      (node (ref "R25") (pin "1") (pinfunction "CCW_1") (pintype "passive"))
    )
    (net (code "51") (name "3.3V") (class "Default")
      (node (ref "C10") (pin "1") (pinfunction "1_1") (pintype "passive"))
      (node (ref "C25") (pin "1") (pinfunction "1_1") (pintype "passive"))
      (node (ref "C42") (pin "+") (pinfunction "+_+") (pintype "passive"))
      (node (ref "FB1") (pin "1") (pinfunction "1_1") (pintype "passive"))
      (node (ref "FB3") (pin "1") (pinfunction "1_1") (pintype "passive"))
      (node (ref "IC3") (pin "3") (pinfunction "OUT_3") (pintype "output"))
      (node (ref "JP5") (pin "1") (pinfunction "1_1") (pintype "passive"))
    )
    (net (code "52") (name "5V") (class "Default")
      (node (ref "C41") (pin "+") (pinfunction "+_+") (pintype "passive"))
      (node (ref "C9") (pin "1") (pinfunction "1_1") (pintype "passive"))
      (node (ref "D12") (pin "1") (pinfunction "C_1") (pintype "passive"))
      (node (ref "FB4") (pin "2") (pinfunction "2_2") (pintype "passive"))
      (node (ref "IC3") (pin "1") (pinfunction "IN_1") (pintype "input"))
      (node (ref "IC4") (pin "18") (pinfunction "AVCC_18") (pintype "bidirectional"))
      (node (ref "IC4") (pin "4") (pinfunction "VCC_4") (pintype "bidirectional"))
      (node (ref "IC4") (pin "6") (pinfunction "VCC_6") (pintype "bidirectional"))
      (node (ref "JP1") (pin "2") (pinfunction "2_2") (pintype "passive"))
      (node (ref "JP2") (pin "2") (pinfunction "2_2") (pintype "passive"))
      (node (ref "JP5") (pin "2") (pinfunction "2_2") (pintype "passive"))
      (node (ref "JP6") (pin "2") (pinfunction "2_2") (pintype "passive"))
      (node (ref "JP8") (pin "2") (pinfunction "2_2") (pintype "passive"))
      (node (ref "JP9") (pin "2") (pinfunction "2_2") (pintype "passive"))
      (node (ref "R15") (pin "1") (pinfunction "1_1") (pintype "passive"))
      (node (ref "R19") (pin "1") (pinfunction "1_1") (pintype "passive"))
      (node (ref "R49") (pin "2") (pinfunction "2_2") (pintype "passive"))
      (node (ref "SG1") (pin "P$2") (pinfunction "2_P$2") (pintype "passive"))
      (node (ref "U1") (pin "1") (pinfunction "1_1") (pintype "passive"))
    )
    (net (code "53") (name "12V") (class "Default")
      (node (ref "C40") (pin "+") (pinfunction "+_+") (pintype "passive"))
      (node (ref "D13") (pin "1") (pinfunction "C_1") (pintype "passive"))
      (node (ref "D3") (pin "1") (pinfunction "C_1") (pintype "passive"))
      (node (ref "JP5") (pin "3") (pinfunction "3_3") (pintype "passive"))
      (node (ref "K1") (pin "2") (pinfunction "1_2") (pintype "passive"))
      (node (ref "K1") (pin "5") (pinfunction "P_5") (pintype "passive"))
      (node (ref "K1") (pin "6") (pinfunction "P_6") (pintype "passive"))
      (node (ref "R23") (pin "2") (pinfunction "2_2") (pintype "passive"))
      (node (ref "R46") (pin "1") (pinfunction "1_1") (pintype "passive"))
      (node (ref "U3") (pin "6") (pinfunction "VCC_6") (pintype "bidirectional"))
    )
    (net (code "54") (name "GND") (class "Default")
      (node (ref "C1") (pin "2") (pinfunction "2_2") (pintype "passive"))
      (node (ref "C10") (pin "2") (pinfunction "2_2") (pintype "passive"))
      (node (ref "C12") (pin "2") (pinfunction "2_2") (pintype "passive"))
      (node (ref "C13") (pin "1") (pinfunction "1_1") (pintype "passive"))
      (node (ref "C14") (pin "1") (pinfunction "1_1") (pintype "passive"))
      (node (ref "C15") (pin "1") (pinfunction "1_1") (pintype "passive"))
      (node (ref "C16") (pin "2") (pinfunction "2_2") (pintype "passive"))
      (node (ref "C17") (pin "2") (pinfunction "2_2") (pintype "passive"))
      (node (ref "C18") (pin "2") (pinfunction "2_2") (pintype "passive"))
      (node (ref "C19") (pin "2") (pinfunction "2_2") (pintype "passive"))
      (node (ref "C2") (pin "2") (pinfunction "2_2") (pintype "passive"))
      (node (ref "C21") (pin "2") (pinfunction "2_2") (pintype "passive"))
      (node (ref "C24") (pin "2") (pinfunction "2_2") (pintype "passive"))
      (node (ref "C25") (pin "2") (pinfunction "2_2") (pintype "passive"))
      (node (ref "C29") (pin "2") (pinfunction "2_2") (pintype "passive"))
      (node (ref "C3") (pin "2") (pinfunction "2_2") (pintype "passive"))
      (node (ref "C30") (pin "-") (pinfunction "-_-") (pintype "passive"))
      (node (ref "C4") (pin "2") (pinfunction "2_2") (pintype "passive"))
      (node (ref "C40") (pin "-") (pinfunction "-_-") (pintype "passive"))
      (node (ref "C41") (pin "-") (pinfunction "-_-") (pintype "passive"))
      (node (ref "C42") (pin "-") (pinfunction "-_-") (pintype "passive"))
      (node (ref "C5") (pin "2") (pinfunction "2_2") (pintype "passive"))
      (node (ref "C6") (pin "2") (pinfunction "2_2") (pintype "passive"))
      (node (ref "C7") (pin "2") (pinfunction "2_2") (pintype "passive"))
      (node (ref "C8") (pin "2") (pinfunction "2_2") (pintype "passive"))
      (node (ref "C9") (pin "2") (pinfunction "2_2") (pintype "passive"))
      (node (ref "D6") (pin "2") (pinfunction "A_2") (pintype "passive"))
      (node (ref "IC1") (pin "10") (pinfunction "GND_10") (pintype "bidirectional"))
      (node (ref "IC1") (pin "13") (pinfunction "GNDA_13") (pintype "bidirectional"))
      (node (ref "IC1") (pin "19") (pinfunction "GNDA_19") (pintype "bidirectional"))
      (node (ref "IC1") (pin "22") (pinfunction "GNDA_22") (pintype "bidirectional"))
      (node (ref "IC1") (pin "24") (pinfunction "GNDA_24") (pintype "bidirectional"))
      (node (ref "IC1") (pin "26") (pinfunction "GND_26") (pintype "bidirectional"))
      (node (ref "IC1") (pin "28") (pinfunction "GND_28") (pintype "bidirectional"))
      (node (ref "IC1") (pin "32") (pinfunction "RSV1_32") (pintype "bidirectional"))
      (node (ref "IC1") (pin "33") (pinfunction "RSV2_33") (pintype "bidirectional"))
      (node (ref "IC1") (pin "34") (pinfunction "RSV3_34") (pintype "bidirectional"))
      (node (ref "IC1") (pin "35") (pinfunction "RSV4_35") (pintype "bidirectional"))
      (node (ref "IC1") (pin "36") (pinfunction "RSV5_36") (pintype "bidirectional"))
      (node (ref "IC1") (pin "37") (pinfunction "RSV6_37") (pintype "bidirectional"))
      (node (ref "IC1") (pin "38") (pinfunction "RSV7_38") (pintype "bidirectional"))
      (node (ref "IC1") (pin "39") (pinfunction "RSV8_39") (pintype "bidirectional"))
      (node (ref "IC1") (pin "48") (pinfunction "GND_48") (pintype "bidirectional"))
      (node (ref "IC1") (pin "9") (pinfunction "GND_9") (pintype "bidirectional"))
      (node (ref "IC1") (pin "EXP@1") (pinfunction "THERM_GND_EXP@1") (pintype "bidirectional"))
      (node (ref "IC1") (pin "EXP@10") (pinfunction "THERM_GND_EXP@10") (pintype "bidirectional"))
      (node (ref "IC1") (pin "EXP@11") (pinfunction "THERM_GND_EXP@11") (pintype "bidirectional"))
      (node (ref "IC1") (pin "EXP@12") (pinfunction "THERM_GND_EXP@12") (pintype "bidirectional"))
      (node (ref "IC1") (pin "EXP@13") (pinfunction "THERM_GND_EXP@13") (pintype "bidirectional"))
      (node (ref "IC1") (pin "EXP@14") (pinfunction "THERM_GND_EXP@14") (pintype "bidirectional"))
      (node (ref "IC1") (pin "EXP@15") (pinfunction "THERM_GND_EXP@15") (pintype "bidirectional"))
      (node (ref "IC1") (pin "EXP@16") (pinfunction "THERM_GND_EXP@16") (pintype "bidirectional"))
      (node (ref "IC1") (pin "EXP@17") (pinfunction "THERM_GND_EXP@17") (pintype "bidirectional"))
      (node (ref "IC1") (pin "EXP@18") (pinfunction "THERM_GND_EXP@18") (pintype "bidirectional"))
      (node (ref "IC1") (pin "EXP@19") (pinfunction "THERM_GND_EXP@19") (pintype "bidirectional"))
      (node (ref "IC1") (pin "EXP@2") (pinfunction "THERM_GND_EXP@2") (pintype "bidirectional"))
      (node (ref "IC1") (pin "EXP@20") (pinfunction "THERM_GND_EXP@20") (pintype "bidirectional"))
      (node (ref "IC1") (pin "EXP@21") (pinfunction "THERM_GND_EXP@21") (pintype "bidirectional"))
      (node (ref "IC1") (pin "EXP@22") (pinfunction "THERM_GND_EXP@22") (pintype "bidirectional"))
      (node (ref "IC1") (pin "EXP@23") (pinfunction "THERM_GND_EXP@23") (pintype "bidirectional"))
      (node (ref "IC1") (pin "EXP@24") (pinfunction "THERM_GND_EXP@24") (pintype "bidirectional"))
      (node (ref "IC1") (pin "EXP@25") (pinfunction "THERM_GND_EXP@25") (pintype "bidirectional"))
      (node (ref "IC1") (pin "EXP@3") (pinfunction "THERM_GND_EXP@3") (pintype "bidirectional"))
      (node (ref "IC1") (pin "EXP@4") (pinfunction "THERM_GND_EXP@4") (pintype "bidirectional"))
      (node (ref "IC1") (pin "EXP@5") (pinfunction "THERM_GND_EXP@5") (pintype "bidirectional"))
      (node (ref "IC1") (pin "EXP@6") (pinfunction "THERM_GND_EXP@6") (pintype "bidirectional"))
      (node (ref "IC1") (pin "EXP@7") (pinfunction "THERM_GND_EXP@7") (pintype "bidirectional"))
      (node (ref "IC1") (pin "EXP@8") (pinfunction "THERM_GND_EXP@8") (pintype "bidirectional"))
      (node (ref "IC1") (pin "EXP@9") (pinfunction "THERM_GND_EXP@9") (pintype "bidirectional"))
      (node (ref "IC2") (pin "2") (pinfunction "GND_2") (pintype "input"))
      (node (ref "IC2") (pin "4") (pinfunction "GND1_4") (pintype "input"))
      (node (ref "IC3") (pin "2") (pinfunction "GND_2") (pintype "input"))
      (node (ref "IC3") (pin "4") (pinfunction "GND1_4") (pintype "input"))
      (node (ref "IC4") (pin "21") (pinfunction "GND_21") (pintype "bidirectional"))
      (node (ref "IC4") (pin "3") (pinfunction "GND_3") (pintype "bidirectional"))
      (node (ref "IC4") (pin "5") (pinfunction "AGND_5") (pintype "bidirectional"))
      (node (ref "IC7") (pin "7") (pinfunction "GND_7") (pintype "bidirectional"))
      (node (ref "JP1") (pin "6") (pinfunction "6_6") (pintype "passive"))
      (node (ref "JP3") (pin "5") (pinfunction "5_5") (pintype "passive"))
      (node (ref "JP3") (pin "6") (pinfunction "6_6") (pintype "passive"))
      (node (ref "JP4") (pin "2") (pinfunction "2_2") (pintype "passive"))
      (node (ref "JP5") (pin "4") (pinfunction "4_4") (pintype "passive"))
      (node (ref "JP8") (pin "1") (pinfunction "1_1") (pintype "passive"))
      (node (ref "JP9") (pin "12") (pinfunction "12_12") (pintype "passive"))
      (node (ref "K2") (pin "4") (pinfunction "P_4") (pintype "passive"))
      (node (ref "LED1") (pin "C") (pinfunction "C_C") (pintype "passive"))
      (node (ref "LED2") (pin "C") (pinfunction "C_C") (pintype "passive"))
      (node (ref "LED3") (pin "C") (pinfunction "C_C") (pintype "passive"))
      (node (ref "Q1") (pin "2") (pinfunction "E_2") (pintype "passive"))
      (node (ref "Q2") (pin "2") (pinfunction "E_2") (pintype "passive"))
      (node (ref "R16") (pin "2") (pinfunction "2_2") (pintype "passive"))
      (node (ref "R4") (pin "1") (pinfunction "1_1") (pintype "passive"))
      (node (ref "R44") (pin "1") (pinfunction "1_1") (pintype "passive"))
      (node (ref "R48") (pin "2") (pinfunction "2_2") (pintype "passive"))
      (node (ref "S1") (pin "1") (pinfunction "1_1") (pintype "passive"))
      (node (ref "S1") (pin "2") (pinfunction "2_2") (pintype "passive"))
      (node (ref "U1") (pin "3") (pinfunction "3_3") (pintype "passive"))
      (node (ref "U1") (pin "5") (pinfunction "5_5") (pintype "passive"))
      (node (ref "U1") (pin "7") (pinfunction "7_7") (pintype "passive"))
      (node (ref "U3") (pin "4") (pinfunction "GND_4") (pintype "bidirectional"))
    )
    (net (code "55") (name "Net-(AG102-THERM)") (class "Default")
      (node (ref "AG102") (pin "7") (pinfunction "THERM_7") (pintype "bidirectional"))
      (node (ref "JP10") (pin "1") (pinfunction "1_1") (pintype "passive"))
    )
    (net (code "56") (name "Net-(AG8100-ADJ)") (class "Default")
      (node (ref "AG8100") (pin "10") (pinfunction "ADJ_10") (pintype "bidirectional"))
      (node (ref "R25") (pin "2") (pinfunction "WIPER_2") (pintype "passive"))
    )
    (net (code "57") (name "Net-(AG8100-CLASS_P)") (class "Default")
      (node (ref "AG8100") (pin "4") (pinfunction "CLASS_P_4") (pintype "bidirectional"))
      (node (ref "R26") (pin "2") (pinfunction "2_2") (pintype "passive"))
    )
    (net (code "58") (name "Net-(C2-Pad1)") (class "Default")
      (node (ref "C2") (pin "1") (pinfunction "1_1") (pintype "passive"))
      (node (ref "C3") (pin "1") (pinfunction "1_1") (pintype "passive"))
      (node (ref "FB2") (pin "2") (pinfunction "2_2") (pintype "passive"))
      (node (ref "IC1") (pin "25") (pinfunction "VCC1V8_25") (pintype "bidirectional"))
      (node (ref "IC1") (pin "8") (pinfunction "VCC1V8_8") (pintype "bidirectional"))
    )
    (net (code "59") (name "Net-(C4-Pad1)") (class "Default")
      (node (ref "C4") (pin "1") (pinfunction "1_1") (pintype "passive"))
      (node (ref "C5") (pin "1") (pinfunction "1_1") (pintype "passive"))
      (node (ref "C6") (pin "1") (pinfunction "1_1") (pintype "passive"))
      (node (ref "FB3") (pin "2") (pinfunction "2_2") (pintype "passive"))
      (node (ref "IC1") (pin "11") (pinfunction "VCC3V3A_11") (pintype "bidirectional"))
      (node (ref "IC1") (pin "15") (pinfunction "VCC3V3A_15") (pintype "bidirectional"))
      (node (ref "IC1") (pin "23") (pinfunction "VCC3V3A_23") (pintype "bidirectional"))
    )
    (net (code "60") (name "Net-(C11-Pad2)") (class "Default")
      (node (ref "C11") (pin "2") (pinfunction "2_2") (pintype "passive"))
      (node (ref "JP3") (pin "1") (pinfunction "1_1") (pintype "passive"))
    )
    (net (code "61") (name "Net-(C14-Pad2)") (class "Default")
      (node (ref "C14") (pin "2") (pinfunction "2_2") (pintype "passive"))
      (node (ref "R28") (pin "1") (pinfunction "1_1") (pintype "passive"))
      (node (ref "R29") (pin "1") (pinfunction "1_1") (pintype "passive"))
    )
    (net (code "62") (name "Net-(C15-Pad2)") (class "Default")
      (node (ref "C15") (pin "2") (pinfunction "2_2") (pintype "passive"))
      (node (ref "R21") (pin "1") (pinfunction "1_1") (pintype "passive"))
      (node (ref "R27") (pin "1") (pinfunction "1_1") (pintype "passive"))
    )
    (net (code "63") (name "Net-(C22-Pad2)") (class "Default")
      (node (ref "C22") (pin "2") (pinfunction "2_2") (pintype "passive"))
      (node (ref "R14") (pin "1") (pinfunction "1_1") (pintype "passive"))
      (node (ref "R20") (pin "1") (pinfunction "1_1") (pintype "passive"))
      (node (ref "R36") (pin "1") (pinfunction "1_1") (pintype "passive"))
      (node (ref "R37") (pin "1") (pinfunction "1_1") (pintype "passive"))
    )
    (net (code "64") (name "Net-(C23-Pad1)") (class "Default")
      (node (ref "C23") (pin "1") (pinfunction "1_1") (pintype "passive"))
      (node (ref "R20") (pin "2") (pinfunction "2_2") (pintype "passive"))
    )
    (net (code "65") (name "Net-(C26-Pad1)") (class "Default")
      (node (ref "C26") (pin "1") (pinfunction "1_1") (pintype "passive"))
      (node (ref "R36") (pin "2") (pinfunction "2_2") (pintype "passive"))
    )
    (net (code "66") (name "Net-(C27-Pad1)") (class "Default")
      (node (ref "C27") (pin "1") (pinfunction "1_1") (pintype "passive"))
      (node (ref "R37") (pin "2") (pinfunction "2_2") (pintype "passive"))
    )
    (net (code "67") (name "Net-(C28-Pad1)") (class "Default")
      (node (ref "C28") (pin "1") (pinfunction "1_1") (pintype "passive"))
      (node (ref "R14") (pin "2") (pinfunction "2_2") (pintype "passive"))
    )
    (net (code "68") (name "Net-(CHARGE_SELECT-Pad2)") (class "Default")
      (node (ref "CHARGE_SELECT") (pin "2") (pinfunction "2_2") (pintype "passive"))
      (node (ref "R43") (pin "2") (pinfunction "2_2") (pintype "passive"))
    )
    (net (code "69") (name "Net-(CHARGE_SELECT-Pad4)") (class "Default")
      (node (ref "CHARGE_SELECT") (pin "4") (pinfunction "4_4") (pintype "passive"))
      (node (ref "R42") (pin "2") (pinfunction "2_2") (pintype "passive"))
    )
    (net (code "70") (name "Net-(CHARGE_SELECT-Pad6)") (class "Default")
      (node (ref "CHARGE_SELECT") (pin "6") (pinfunction "6_6") (pintype "passive"))
      (node (ref "R41") (pin "2") (pinfunction "2_2") (pintype "passive"))
    )
    (net (code "71") (name "Net-(CHARGE_SELECT-Pad8)") (class "Default")
      (node (ref "CHARGE_SELECT") (pin "8") (pinfunction "8_8") (pintype "passive"))
      (node (ref "R40") (pin "2") (pinfunction "2_2") (pintype "passive"))
    )
    (net (code "72") (name "Net-(D3-A)") (class "Default")
      (node (ref "D3") (pin "2") (pinfunction "A_2") (pintype "passive"))
      (node (ref "K1") (pin "9") (pinfunction "2_9") (pintype "passive"))
      (node (ref "LED5") (pin "C") (pinfunction "C_C") (pintype "passive"))
      (node (ref "Q1") (pin "3") (pinfunction "C_3") (pintype "passive"))
    )
    (net (code "73") (name "Net-(D6-C)") (class "Default")
      (node (ref "D6") (pin "1") (pinfunction "C_1") (pintype "passive"))
      (node (ref "L1") (pin "P$1") (pinfunction "1_P$1") (pintype "passive"))
      (node (ref "U3") (pin "2") (pinfunction "SWE_2") (pintype "bidirectional"))
    )
    (net (code "74") (name "Net-(D12-A)") (class "Default")
      (node (ref "D12") (pin "2") (pinfunction "A_2") (pintype "passive"))
      (node (ref "JP3") (pin "4") (pinfunction "4_4") (pintype "passive"))
    )
    (net (code "75") (name "Net-(D13-A)") (class "Default")
      (node (ref "D13") (pin "2") (pinfunction "A_2") (pintype "passive"))
      (node (ref "K2") (pin "13") (pinfunction "P_13") (pintype "passive"))
    )
    (net (code "76") (name "Net-(IC1-*FDX_LED)") (class "Default")
      (node (ref "IC1") (pin "3") (pinfunction "*FDX_LED_3") (pintype "bidirectional"))
      (node (ref "LED6") (pin "A") (pinfunction "A_A") (pintype "passive"))
      (node (ref "R7") (pin "2") (pinfunction "2_2") (pintype "passive"))
    )
    (net (code "77") (name "Net-(IC1-ANE)") (class "Default")
      (node (ref "IC1") (pin "29") (pinfunction "ANE_29") (pintype "bidirectional"))
      (node (ref "R1") (pin "2") (pinfunction "2_2") (pintype "passive"))
    )
    (net (code "78") (name "Net-(IC1-BIAS)") (class "Default")
      (node (ref "IC1") (pin "12") (pinfunction "BIAS_12") (pintype "bidirectional"))
      (node (ref "R48") (pin "1") (pinfunction "1_1") (pintype "passive"))
    )
    (net (code "79") (name "Net-(IC1-DUP)") (class "Default")
      (node (ref "IC1") (pin "30") (pinfunction "DUP_30") (pintype "bidirectional"))
      (node (ref "R5") (pin "2") (pinfunction "2_2") (pintype "passive"))
    )
    (net (code "80") (name "Net-(IC1-M6)") (class "Default")
      (node (ref "IC1") (pin "6") (pinfunction "M6_6") (pintype "bidirectional"))
      (node (ref "R10") (pin "2") (pinfunction "2_2") (pintype "passive"))
    )
    (net (code "81") (name "Net-(IC1-RSV0)") (class "Default")
      (node (ref "IC1") (pin "7") (pinfunction "RSV0_7") (pintype "bidirectional"))
      (node (ref "R11") (pin "2") (pinfunction "2_2") (pintype "passive"))
    )
    (net (code "82") (name "Net-(IC1-SPD)") (class "Default")
      (node (ref "IC1") (pin "31") (pinfunction "SPD_31") (pintype "bidirectional"))
      (node (ref "R6") (pin "2") (pinfunction "2_2") (pintype "passive"))
    )
    (net (code "83") (name "Net-(IC1-VCC1V8O)") (class "Default")
      (node (ref "C21") (pin "1") (pinfunction "1_1") (pintype "passive"))
      (node (ref "FB2") (pin "1") (pinfunction "1_1") (pintype "passive"))
      (node (ref "IC1") (pin "14") (pinfunction "VCC1V8O_14") (pintype "bidirectional"))
    )
    (net (code "84") (name "Net-(IC1-XI)") (class "Default")
      (node (ref "C17") (pin "1") (pinfunction "1_1") (pintype "passive"))
      (node (ref "IC1") (pin "1") (pinfunction "XI_1") (pintype "bidirectional"))
      (node (ref "R2") (pin "2") (pinfunction "2_2") (pintype "passive"))
      (node (ref "Y1") (pin "P$3") (pinfunction "2_P$3") (pintype "passive"))
    )
    (net (code "85") (name "Net-(IC1-XO)") (class "Default")
      (node (ref "C16") (pin "1") (pinfunction "1_1") (pintype "passive"))
      (node (ref "IC1") (pin "2") (pinfunction "XO_2") (pintype "bidirectional"))
      (node (ref "R2") (pin "1") (pinfunction "1_1") (pintype "passive"))
      (node (ref "Y1") (pin "P$1") (pinfunction "1_P$1") (pintype "passive"))
    )
    (net (code "86") (name "Net-(IC1-XTALVDD)") (class "Default")
      (node (ref "C1") (pin "1") (pinfunction "1_1") (pintype "passive"))
      (node (ref "C24") (pin "1") (pinfunction "1_1") (pintype "passive"))
      (node (ref "IC1") (pin "16") (pinfunction "XTALVDD_16") (pintype "bidirectional"))
    )
    (net (code "87") (name "Net-(IC2-OUT)") (class "Default")
      (node (ref "FB4") (pin "1") (pinfunction "1_1") (pintype "passive"))
      (node (ref "IC2") (pin "3") (pinfunction "OUT_3") (pintype "output"))
    )
    (net (code "88") (name "Net-(IC4-AREF)") (class "Default")
      (node (ref "C12") (pin "1") (pinfunction "1_1") (pintype "passive"))
      (node (ref "IC4") (pin "20") (pinfunction "AREF_20") (pintype "bidirectional"))
    )
    (net (code "89") (name "Net-(IC4-PB6(XTAL1{slash}TOSC1))") (class "Default")
      (node (ref "C18") (pin "1") (pinfunction "1_1") (pintype "passive"))
      (node (ref "IC4") (pin "7") (pinfunction "PB6(XTAL1/TOSC1)_7") (pintype "bidirectional"))
      (node (ref "R3") (pin "2") (pinfunction "2_2") (pintype "passive"))
      (node (ref "Y2") (pin "1") (pinfunction "P$1_1") (pintype "bidirectional"))
    )
    (net (code "90") (name "Net-(IC4-PB7(XTAL2{slash}TOSC2))") (class "Default")
      (node (ref "C19") (pin "1") (pinfunction "1_1") (pintype "passive"))
      (node (ref "IC4") (pin "8") (pinfunction "PB7(XTAL2/TOSC2)_8") (pintype "bidirectional"))
      (node (ref "R3") (pin "1") (pinfunction "1_1") (pintype "passive"))
      (node (ref "Y2") (pin "3") (pinfunction "P$2_3") (pintype "bidirectional"))
    )
    (net (code "91") (name "Net-(IC7-RST)") (class "Default")
      (node (ref "IC7") (pin "3") (pinfunction "RST_3") (pintype "bidirectional"))
      (node (ref "R18") (pin "1") (pinfunction "1_1") (pintype "passive"))
    )
    (net (code "92") (name "Net-(K1B-O)") (class "Default")
      (node (ref "JP4") (pin "3") (pinfunction "3_3") (pintype "passive"))
      (node (ref "K1") (pin "1") (pinfunction "O_1") (pintype "passive"))
    )
    (net (code "93") (name "Net-(K1B-S)") (class "Default")
      (node (ref "JP4") (pin "1") (pinfunction "1_1") (pintype "passive"))
      (node (ref "K1") (pin "10") (pinfunction "S_10") (pintype "passive"))
    )
    (net (code "94") (name "Net-(LED1-PadA)") (class "Default")
      (node (ref "LED1") (pin "A") (pinfunction "A_A") (pintype "passive"))
      (node (ref "R35") (pin "2") (pinfunction "2_2") (pintype "passive"))
      (node (ref "SEL_L1") (pin "3") (pinfunction "3_3") (pintype "passive"))
    )
    (net (code "95") (name "Net-(LED2-PadA)") (class "Default")
      (node (ref "LED2") (pin "A") (pinfunction "A_A") (pintype "passive"))
      (node (ref "R34") (pin "2") (pinfunction "2_2") (pintype "passive"))
      (node (ref "SEL_L2") (pin "3") (pinfunction "3_3") (pintype "passive"))
    )
    (net (code "96") (name "Net-(LED3-PadA)") (class "Default")
      (node (ref "LED3") (pin "A") (pinfunction "A_A") (pintype "passive"))
      (node (ref "R33") (pin "2") (pinfunction "2_2") (pintype "passive"))
      (node (ref "SEL_L3") (pin "3") (pinfunction "3_3") (pintype "passive"))
    )
    (net (code "97") (name "Net-(LED4-PadA)") (class "Default")
      (node (ref "LED4") (pin "A") (pinfunction "A_A") (pintype "passive"))
      (node (ref "R22") (pin "1") (pinfunction "1_1") (pintype "passive"))
    )
    (net (code "98") (name "Net-(LED5-PadA)") (class "Default")
      (node (ref "LED5") (pin "A") (pinfunction "A_A") (pintype "passive"))
      (node (ref "R23") (pin "1") (pinfunction "1_1") (pintype "passive"))
    )
    (net (code "99") (name "Net-(LED6-PadC)") (class "Default")
      (node (ref "LED6") (pin "C") (pinfunction "C_C") (pintype "passive"))
      (node (ref "R32") (pin "2") (pinfunction "2_2") (pintype "passive"))
    )
    (net (code "100") (name "Net-(LED7-PadA)") (class "Default")
      (node (ref "LED7") (pin "A") (pinfunction "A_A") (pintype "passive"))
      (node (ref "R47") (pin "2") (pinfunction "2_2") (pintype "passive"))
    )
    (net (code "101") (name "Net-(Q1-B)") (class "Default")
      (node (ref "Q1") (pin "1") (pinfunction "B_1") (pintype "passive"))
      (node (ref "R24") (pin "2") (pinfunction "2_2") (pintype "passive"))
    )
    (net (code "102") (name "Net-(Q2-B)") (class "Default")
      (node (ref "Q2") (pin "1") (pinfunction "B_1") (pintype "passive"))
      (node (ref "R17") (pin "2") (pinfunction "2_2") (pintype "passive"))
    )
    (net (code "103") (name "Net-(SEL_L1-Pad2)") (class "Default")
      (node (ref "SEL_L1") (pin "2") (pinfunction "2_2") (pintype "passive"))
      (node (ref "U1") (pin "8") (pinfunction "8_8") (pintype "passive"))
    )
    (net (code "104") (name "Net-(SEL_L2-Pad2)") (class "Default")
      (node (ref "SEL_L2") (pin "2") (pinfunction "2_2") (pintype "passive"))
      (node (ref "U1") (pin "6") (pinfunction "6_6") (pintype "passive"))
    )
    (net (code "105") (name "Net-(SEL_L3-Pad2)") (class "Default")
      (node (ref "SEL_L3") (pin "2") (pinfunction "2_2") (pintype "passive"))
      (node (ref "U1") (pin "4") (pinfunction "4_4") (pintype "passive"))
    )
    (net (code "106") (name "Net-(SEL_L4-Pad2)") (class "Default")
      (node (ref "SEL_L4") (pin "2") (pinfunction "2_2") (pintype "passive"))
      (node (ref "U1") (pin "2") (pinfunction "2_2") (pintype "passive"))
    )
    (net (code "107") (name "Net-(U2-LED1_A)") (class "Default")
      (node (ref "R31") (pin "1") (pinfunction "1_1") (pintype "passive"))
      (node (ref "U2") (pin "9") (pinfunction "LED1_A_9") (pintype "bidirectional"))
    )
    (net (code "108") (name "Net-(U2-LED2_A)") (class "Default")
      (node (ref "R30") (pin "1") (pinfunction "1_1") (pintype "passive"))
      (node (ref "U2") (pin "11") (pinfunction "LED2_A_11") (pintype "bidirectional"))
    )
    (net (code "109") (name "Net-(U3-COMP)") (class "Default")
      (node (ref "R44") (pin "2") (pinfunction "2_2") (pintype "passive"))
      (node (ref "R45") (pin "2") (pinfunction "2_2") (pintype "passive"))
      (node (ref "U3") (pin "5") (pinfunction "COMP_5") (pintype "bidirectional"))
    )
    (net (code "110") (name "Net-(U3-DVR)") (class "Default")
      (node (ref "R46") (pin "2") (pinfunction "2_2") (pintype "passive"))
      (node (ref "U3") (pin "1") (pinfunction "SWC_1") (pintype "bidirectional"))
      (node (ref "U3") (pin "7") (pinfunction "SEN_7") (pintype "bidirectional"))
      (node (ref "U3") (pin "8") (pinfunction "DVR_8") (pintype "bidirectional"))
    )
    (net (code "111") (name "Net-(U3-TC)") (class "Default")
      (node (ref "C29") (pin "1") (pinfunction "1_1") (pintype "passive"))
      (node (ref "U3") (pin "3") (pinfunction "TC_3") (pintype "bidirectional"))
    )
    (net (code "112") (name "unconnected-(R25-CW-Pad3)") (class "Default")
      (node (ref "R25") (pin "3") (pinfunction "CW_3") (pintype "passive"))
    )
  )
)
